# 1_AIR_TEST.net
KiCad netlist of a schematic drawn in Altium Designer
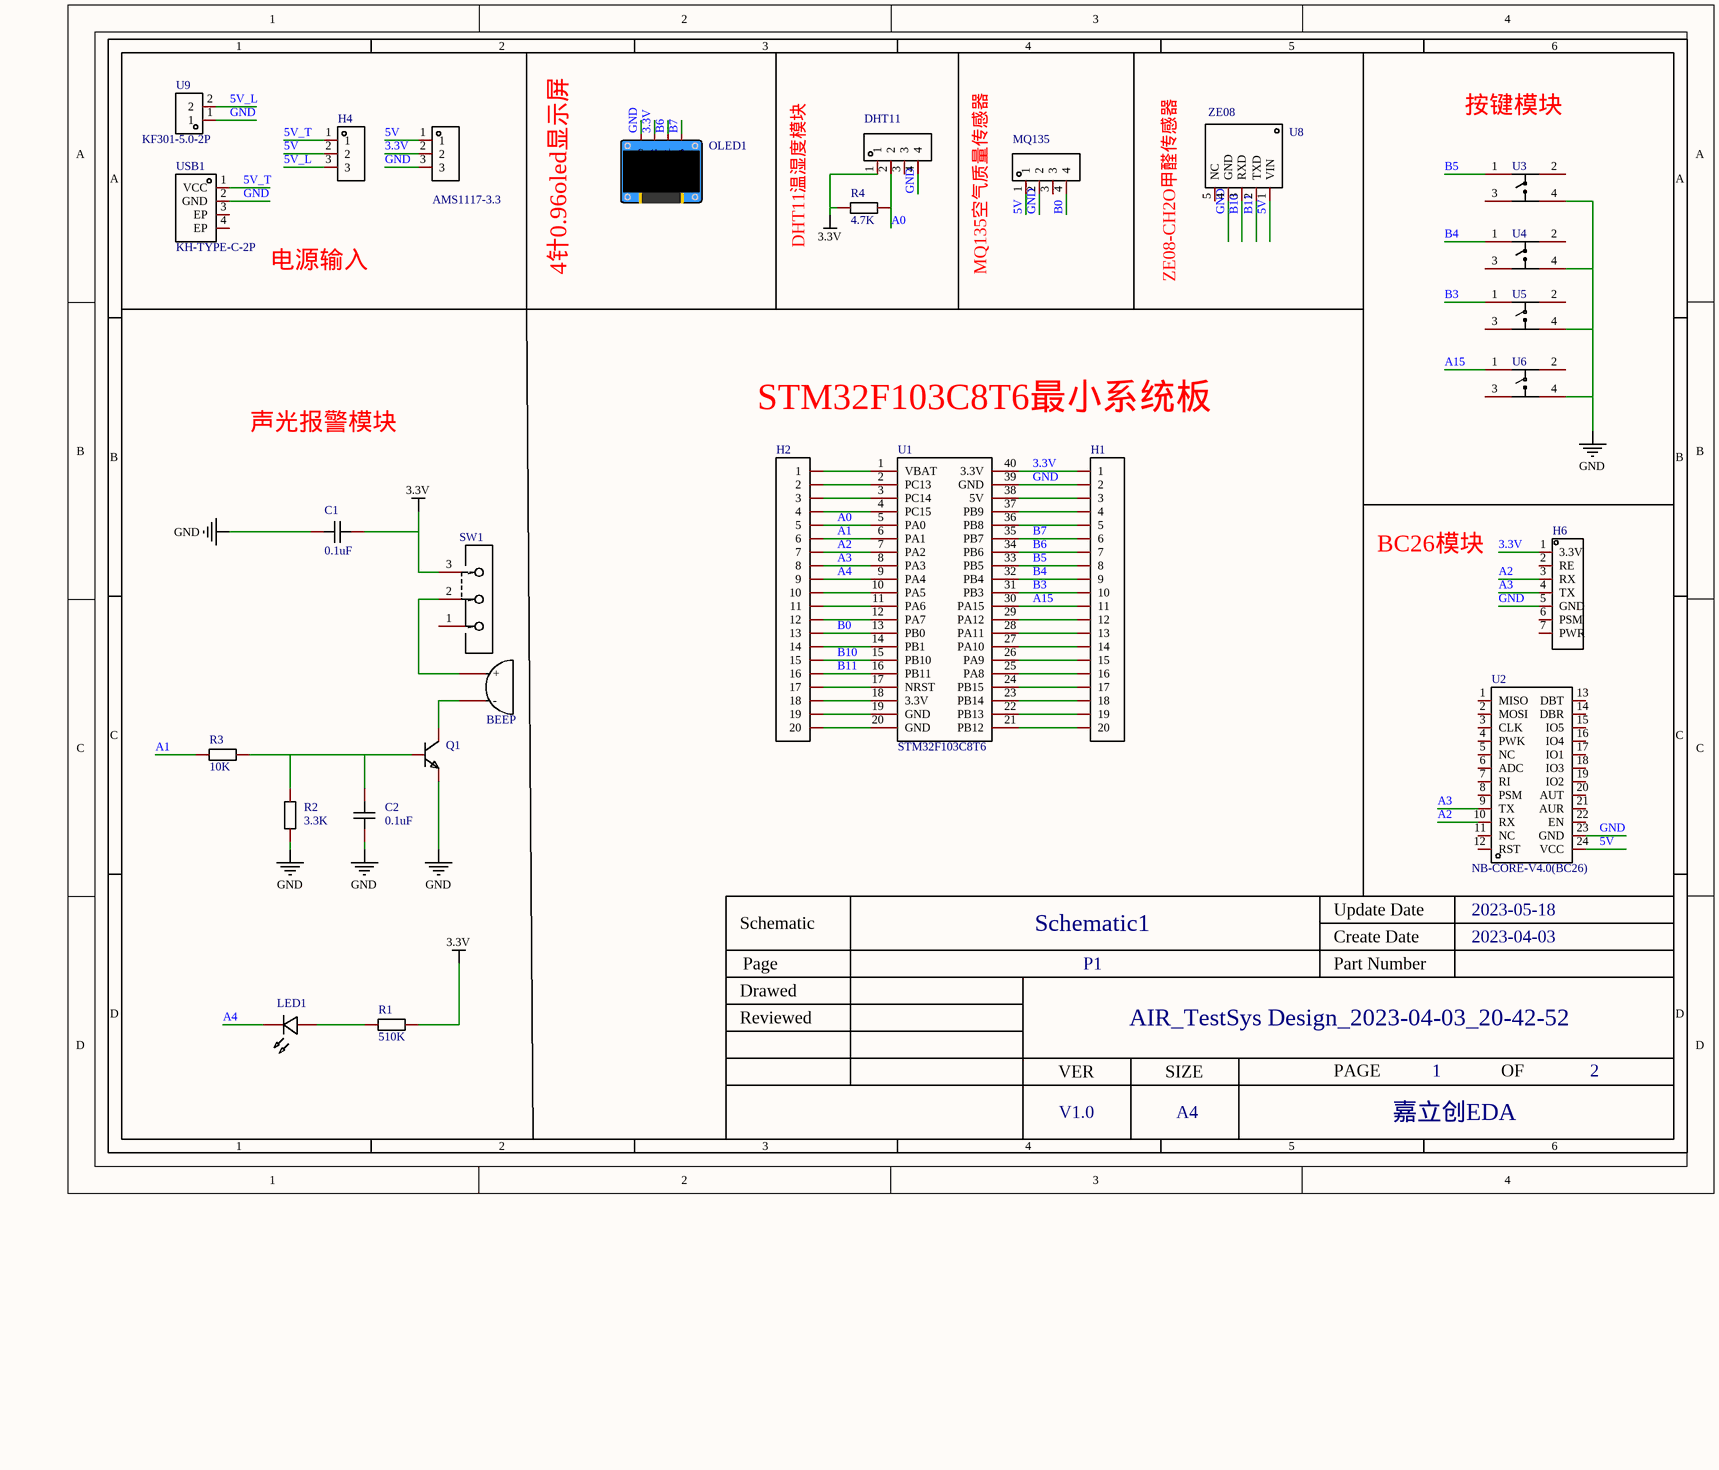
[diagram p0: 1_AIR_TEST.schdoc]

(export (version "E")
  (design (tool "Eeschema 10.0.6"))
  (components
    (comp (ref "BEEP1")
      (value "BEEP")
      (fields (field (name "NAME") "BEEP"))
      (libsource (lib "altium-import") (part "root_3_BEEP_"))
    )
    (comp (ref "C1")
      (value "0.1uF")
      (fields (field (name "NAME") "0.1uF"))
      (libsource (lib "altium-import") (part "root_0_CAP_0603_"))
    )
    (comp (ref "C2")
      (value "0.1uF")
      (fields (field (name "NAME") "0.1uF"))
      (libsource (lib "altium-import") (part "root_1_CAP_0603_"))
    )
    (comp (ref "DHT11")
      (value "HDR-F_2.54_1x4P")
      (libsource (lib "altium-import") (part "root_1_HDR-F_2.54_1x4P_"))
    )
    (comp (ref "H1")
      (value "HDR-F_2.54_1x20P")
      (libsource (lib "altium-import") (part "root_0_HDR-F_2.54_1x20P_"))
    )
    (comp (ref "H2")
      (value "HDR-F_2.54_1x20P")
      (libsource (lib "altium-import") (part "root_0_mirrored_HDR-F_2.54_1x20P_"))
    )
    (comp (ref "H4")
      (value "HDR-F_2.54_1x3P")
      (libsource (lib "altium-import") (part "root_0_HDR-F_2.54_1x3P_"))
    )
    (comp (ref "H6")
      (value "HDR-F_2.54_1x7P")
      (libsource (lib "altium-import") (part "root_0_HDR-F_2.54_1x7P_"))
    )
    (comp (ref "LED1") (value "LED_TH-R_3mm") (libsource (lib "altium-import") (part "root_2_LED_TH-R_3mm_")))
    (comp (ref "MQ135")
      (value "HDR-F_2.54_1x4P")
      (libsource (lib "altium-import") (part "root_1_HDR-F_2.54_1x4P_"))
    )
    (comp (ref "OLED1")
      (value "0.96OLED模块_4P")
      (libsource (lib "altium-import") (part "root_0_0.96OLED模块_4P_"))
    )
    (comp (ref "Q1") (value "S8050_TO_NPN") (libsource (lib "altium-import") (part "root_0_S8050_TO_NPN_")))
    (comp (ref "R1")
      (value "510K")
      (fields (field (name "NAME") "510K"))
      (libsource (lib "altium-import") (part "root_0_Res_0603_"))
    )
    (comp (ref "R2")
      (value "3.3K")
      (fields (field (name "NAME") "3.3K"))
      (libsource (lib "altium-import") (part "root_1_Res_0603_"))
    )
    (comp (ref "R3")
      (value "10K")
      (fields (field (name "NAME") "10K"))
      (libsource (lib "altium-import") (part "root_0_Res_0603_"))
    )
    (comp (ref "R4")
      (value "4.7K")
      (fields (field (name "NAME") "4.7K"))
      (libsource (lib "altium-import") (part "root_0_Res_0603_"))
    )
    (comp (ref "SW1")
      (value "ss-12d00-g4拨动开关")
      (fields (field (name "MANUFACTURER PART") "SS-12d00-G4"))
      (libsource (lib "altium-import") (part "root_1_ss-12d00-g4拨动开关_"))
    )
    (comp (ref "U1")
      (value "STM32F103C8T6")
      (fields
        (field (name "NAME") "STM32F103C8T6")
        (field (name "MANUFACTURER") "无")
        (field (name "MANUFACTURER PART") "STM32F103C8T6最小系统模块")
      )
      (libsource (lib "altium-import") (part "root_0_STM32F103C8T6_"))
    )
    (comp (ref "U2")
      (value "NB-CORE-V4.0(BC26)")
      (fields (field (name "NAME") "NB-CORE-V4.0(BC26)"))
      (libsource (lib "altium-import") (part "root_0_NB-CORE-V4.0(BC26)_"))
    )
    (comp (ref "U3") (value "四角按键") (libsource (lib "altium-import") (part "root_0_四角按键_")))
    (comp (ref "U4") (value "四角按键") (libsource (lib "altium-import") (part "root_0_四角按键_")))
    (comp (ref "U5") (value "四角按键") (libsource (lib "altium-import") (part "root_0_四角按键_")))
    (comp (ref "U6") (value "四角按键") (libsource (lib "altium-import") (part "root_0_四角按键_")))
    (comp (ref "U7")
      (value "AMS1117-3.3")
      (fields (field (name "NAME") "AMS1117-3.3"))
      (libsource (lib "altium-import") (part "root_0_HDR-F_2.54_1x3P_"))
    )
    (comp (ref "U8")
      (value "ZE08")
      (fields (field (name "NAME") "ZE08"))
      (libsource (lib "altium-import") (part "root_3_ZE08B_"))
    )
    (comp (ref "U9")
      (value "KF301-5.0-2P")
      (fields (field (name "NAME") "KF301-5.0-2P") (field (name "MANUFACTURER") "Cixi Kefa Elec"))
      (libsource (lib "altium-import") (part "root_2_KF301-5.0-2P_"))
    )
    (comp (ref "USB1")
      (value "KH-TYPE-C-2P")
      (description "连接器类型:Type-C;标准:-;公母:母座;触点数量:2;端口数量:1;安装方式:弯插;额定电流 - 电源:-;工作温度范围:-25℃~+85℃;")
      (fields (field (name "NAME") "KH-TYPE-C-2P") (field (name "MANUFACTURER") "kinghelm(金航标)"))
      (libsource (lib "altium-import") (part "root_0_mirrored_KH-TYPE-C-2P_"))
    )
  )
  (nets
    (net (code "1") (name "/5V") (class "Default")
      (node (ref "H4") (pin "2") (pinfunction "2_2") (pintype "passive"))
      (node (ref "MQ135") (pin "1") (pinfunction "1_1") (pintype "passive"))
      (node (ref "U2") (pin "24") (pinfunction "VCC_24") (pintype "passive"))
      (node (ref "U7") (pin "1") (pinfunction "1_1") (pintype "passive"))
      (node (ref "U8") (pin "1") (pinfunction "VIN_1") (pintype "passive"))
    )
    (net (code "2") (name "/5V_L") (class "Default")
      (node (ref "H4") (pin "3") (pinfunction "3_3") (pintype "passive"))
      (node (ref "U9") (pin "2") (pinfunction "2_2") (pintype "passive"))
    )
    (net (code "3") (name "/5V_T") (class "Default")
      (node (ref "H4") (pin "1") (pinfunction "1_1") (pintype "passive"))
      (node (ref "USB1") (pin "1") (pinfunction "VCC_1") (pintype "passive"))
    )
    (net (code "4") (name "/A0") (class "Default")
      (node (ref "DHT11") (pin "2") (pinfunction "2_2") (pintype "passive"))
      (node (ref "H2") (pin "5") (pinfunction "5_5") (pintype "passive"))
      (node (ref "R4") (pin "2") (pinfunction "2_2") (pintype "passive"))
      (node (ref "U1") (pin "5") (pinfunction "PA0_5") (pintype "passive"))
    )
    (net (code "5") (name "/A1") (class "Default")
      (node (ref "H2") (pin "6") (pinfunction "6_6") (pintype "passive"))
      (node (ref "R3") (pin "1") (pinfunction "1_1") (pintype "passive"))
      (node (ref "U1") (pin "6") (pinfunction "PA1_6") (pintype "passive"))
    )
    (net (code "6") (name "/A2") (class "Default")
      (node (ref "H2") (pin "7") (pinfunction "7_7") (pintype "passive"))
      (node (ref "H6") (pin "3") (pinfunction "RX_3") (pintype "passive"))
      (node (ref "U1") (pin "7") (pinfunction "PA2_7") (pintype "passive"))
      (node (ref "U2") (pin "10") (pinfunction "RX_10") (pintype "passive"))
    )
    (net (code "7") (name "/A3") (class "Default")
      (node (ref "H2") (pin "8") (pinfunction "8_8") (pintype "passive"))
      (node (ref "H6") (pin "4") (pinfunction "TX_4") (pintype "passive"))
      (node (ref "U1") (pin "8") (pinfunction "PA3_8") (pintype "passive"))
      (node (ref "U2") (pin "9") (pinfunction "TX_9") (pintype "passive"))
    )
    (net (code "8") (name "/A4") (class "Default")
      (node (ref "H2") (pin "9") (pinfunction "9_9") (pintype "passive"))
      (node (ref "LED1") (pin "2") (pinfunction "A_2") (pintype "passive"))
      (node (ref "U1") (pin "9") (pinfunction "PA4_9") (pintype "passive"))
    )
    (net (code "9") (name "/A15") (class "Default")
      (node (ref "H1") (pin "11") (pinfunction "11_11") (pintype "passive"))
      (node (ref "U1") (pin "30") (pinfunction "PA15_30") (pintype "passive"))
      (node (ref "U6") (pin "1") (pinfunction "1_1") (pintype "passive"))
    )
    (net (code "10") (name "/B0") (class "Default")
      (node (ref "H2") (pin "13") (pinfunction "13_13") (pintype "passive"))
      (node (ref "MQ135") (pin "4") (pinfunction "4_4") (pintype "passive"))
      (node (ref "U1") (pin "13") (pinfunction "PB0_13") (pintype "passive"))
    )
    (net (code "11") (name "/B3") (class "Default")
      (node (ref "H1") (pin "10") (pinfunction "10_10") (pintype "passive"))
      (node (ref "U1") (pin "31") (pinfunction "PB3_31") (pintype "passive"))
      (node (ref "U5") (pin "1") (pinfunction "1_1") (pintype "passive"))
    )
    (net (code "12") (name "/B4") (class "Default")
      (node (ref "H1") (pin "9") (pinfunction "9_9") (pintype "passive"))
      (node (ref "U1") (pin "32") (pinfunction "PB4_32") (pintype "passive"))
      (node (ref "U4") (pin "1") (pinfunction "1_1") (pintype "passive"))
    )
    (net (code "13") (name "/B5") (class "Default")
      (node (ref "H1") (pin "8") (pinfunction "8_8") (pintype "passive"))
      (node (ref "U1") (pin "33") (pinfunction "PB5_33") (pintype "passive"))
      (node (ref "U3") (pin "1") (pinfunction "1_1") (pintype "passive"))
    )
    (net (code "14") (name "/B6") (class "Default")
      (node (ref "H1") (pin "7") (pinfunction "7_7") (pintype "passive"))
      (node (ref "OLED1") (pin "3") (pinfunction "SCL_3") (pintype "passive"))
      (node (ref "U1") (pin "34") (pinfunction "PB6_34") (pintype "passive"))
    )
    (net (code "15") (name "/B7") (class "Default")
      (node (ref "H1") (pin "6") (pinfunction "6_6") (pintype "passive"))
      (node (ref "OLED1") (pin "4") (pinfunction "SDA_4") (pintype "passive"))
      (node (ref "U1") (pin "35") (pinfunction "PB7_35") (pintype "passive"))
    )
    (net (code "16") (name "/B10") (class "Default")
      (node (ref "H2") (pin "15") (pinfunction "15_15") (pintype "passive"))
      (node (ref "U1") (pin "15") (pinfunction "PB10_15") (pintype "passive"))
      (node (ref "U8") (pin "3") (pinfunction "RXD_3") (pintype "passive"))
    )
    (net (code "17") (name "/B11") (class "Default")
      (node (ref "H2") (pin "16") (pinfunction "16_16") (pintype "passive"))
      (node (ref "U1") (pin "16") (pinfunction "PB11_16") (pintype "passive"))
      (node (ref "U8") (pin "2") (pinfunction "TXD_2") (pintype "passive"))
    )
    (net (code "18") (name "3.3V") (class "Default")
      (node (ref "C1") (pin "2") (pinfunction "2_2") (pintype "passive"))
      (node (ref "DHT11") (pin "1") (pinfunction "1_1") (pintype "passive"))
      (node (ref "H1") (pin "1") (pinfunction "1_1") (pintype "passive"))
      (node (ref "H6") (pin "1") (pinfunction "3.3V_1") (pintype "passive"))
      (node (ref "OLED1") (pin "2") (pinfunction "VCC_2") (pintype "passive"))
      (node (ref "R1") (pin "2") (pinfunction "2_2") (pintype "passive"))
      (node (ref "R4") (pin "1") (pinfunction "1_1") (pintype "passive"))
      (node (ref "SW1") (pin "3") (pinfunction "3_3") (pintype "passive"))
      (node (ref "U1") (pin "40") (pinfunction "3.3V_40") (pintype "passive"))
      (node (ref "U7") (pin "2") (pinfunction "2_2") (pintype "passive"))
    )
    (net (code "19") (name "GND") (class "Default")
      (node (ref "C1") (pin "1") (pinfunction "1_1") (pintype "passive"))
      (node (ref "C2") (pin "1") (pinfunction "1_1") (pintype "passive"))
      (node (ref "DHT11") (pin "4") (pinfunction "4_4") (pintype "passive"))
      (node (ref "H1") (pin "2") (pinfunction "2_2") (pintype "passive"))
      (node (ref "H6") (pin "5") (pinfunction "GND_5") (pintype "passive"))
      (node (ref "MQ135") (pin "2") (pinfunction "2_2") (pintype "passive"))
      (node (ref "OLED1") (pin "1") (pinfunction "GND_1") (pintype "passive"))
      (node (ref "Q1") (pin "1") (pinfunction "E_1") (pintype "passive"))
      (node (ref "R2") (pin "1") (pinfunction "1_1") (pintype "passive"))
      (node (ref "U1") (pin "39") (pinfunction "GND_39") (pintype "passive"))
      (node (ref "U2") (pin "23") (pinfunction "GND_23") (pintype "passive"))
      (node (ref "U3") (pin "4") (pinfunction "4_4") (pintype "passive"))
      (node (ref "U4") (pin "4") (pinfunction "4_4") (pintype "passive"))
      (node (ref "U5") (pin "4") (pinfunction "4_4") (pintype "passive"))
      (node (ref "U6") (pin "4") (pinfunction "4_4") (pintype "passive"))
      (node (ref "U7") (pin "3") (pinfunction "3_3") (pintype "passive"))
      (node (ref "U8") (pin "4") (pinfunction "GND_4") (pintype "passive"))
      (node (ref "U9") (pin "1") (pinfunction "1_1") (pintype "passive"))
      (node (ref "USB1") (pin "2") (pinfunction "GND_2") (pintype "passive"))
    )
    (net (code "20") (name "Net-(BEEP1-+)") (class "Default")
      (node (ref "BEEP1") (pin "1") (pinfunction "+_1") (pintype "passive"))
      (node (ref "SW1") (pin "2") (pinfunction "2_2") (pintype "passive"))
    )
    (net (code "21") (name "Net-(BEEP1--)") (class "Default")
      (node (ref "BEEP1") (pin "2") (pinfunction "-_2") (pintype "passive"))
      (node (ref "Q1") (pin "3") (pinfunction "C_3") (pintype "passive"))
    )
    (net (code "22") (name "Net-(H2-Pad18)") (class "Default")
      (node (ref "H2") (pin "18") (pinfunction "18_18") (pintype "passive"))
      (node (ref "U1") (pin "18") (pinfunction "3.3V_18") (pintype "passive"))
    )
    (net (code "23") (name "Net-(H2-Pad19)") (class "Default")
      (node (ref "H2") (pin "19") (pinfunction "19_19") (pintype "passive"))
      (node (ref "U1") (pin "19") (pinfunction "GND_19") (pintype "passive"))
    )
    (net (code "24") (name "Net-(H2-Pad20)") (class "Default")
      (node (ref "H2") (pin "20") (pinfunction "20_20") (pintype "passive"))
      (node (ref "U1") (pin "20") (pinfunction "GND_20") (pintype "passive"))
    )
    (net (code "25") (name "Net-(LED1-C)") (class "Default")
      (node (ref "LED1") (pin "1") (pinfunction "C_1") (pintype "passive"))
      (node (ref "R1") (pin "1") (pinfunction "1_1") (pintype "passive"))
    )
    (net (code "26") (name "Net-(Q1-B)") (class "Default")
      (node (ref "C2") (pin "2") (pinfunction "2_2") (pintype "passive"))
      (node (ref "Q1") (pin "2") (pinfunction "B_2") (pintype "passive"))
      (node (ref "R2") (pin "2") (pinfunction "2_2") (pintype "passive"))
      (node (ref "R3") (pin "2") (pinfunction "2_2") (pintype "passive"))
    )
    (net (code "27") (name "Net-(U1-5V)") (class "Default")
      (node (ref "H1") (pin "3") (pinfunction "3_3") (pintype "passive"))
      (node (ref "U1") (pin "38") (pinfunction "5V_38") (pintype "passive"))
    )
    (net (code "28") (name "Net-(U1-NRST)") (class "Default")
      (node (ref "H2") (pin "17") (pinfunction "17_17") (pintype "passive"))
      (node (ref "U1") (pin "17") (pinfunction "NRST_17") (pintype "passive"))
    )
    (net (code "29") (name "Net-(U1-PA5)") (class "Default")
      (node (ref "H2") (pin "10") (pinfunction "10_10") (pintype "passive"))
      (node (ref "U1") (pin "10") (pinfunction "PA5_10") (pintype "passive"))
    )
    (net (code "30") (name "Net-(U1-PA6)") (class "Default")
      (node (ref "H2") (pin "11") (pinfunction "11_11") (pintype "passive"))
      (node (ref "U1") (pin "11") (pinfunction "PA6_11") (pintype "passive"))
    )
    (net (code "31") (name "Net-(U1-PA7)") (class "Default")
      (node (ref "H2") (pin "12") (pinfunction "12_12") (pintype "passive"))
      (node (ref "U1") (pin "12") (pinfunction "PA7_12") (pintype "passive"))
    )
    (net (code "32") (name "Net-(U1-PA8)") (class "Default")
      (node (ref "H1") (pin "16") (pinfunction "16_16") (pintype "passive"))
      (node (ref "U1") (pin "25") (pinfunction "PA8_25") (pintype "passive"))
    )
    (net (code "33") (name "Net-(U1-PA9)") (class "Default")
      (node (ref "H1") (pin "15") (pinfunction "15_15") (pintype "passive"))
      (node (ref "U1") (pin "26") (pinfunction "PA9_26") (pintype "passive"))
    )
    (net (code "34") (name "Net-(U1-PA10)") (class "Default")
      (node (ref "H1") (pin "14") (pinfunction "14_14") (pintype "passive"))
      (node (ref "U1") (pin "27") (pinfunction "PA10_27") (pintype "passive"))
    )
    (net (code "35") (name "Net-(U1-PA11)") (class "Default")
      (node (ref "H1") (pin "13") (pinfunction "13_13") (pintype "passive"))
      (node (ref "U1") (pin "28") (pinfunction "PA11_28") (pintype "passive"))
    )
    (net (code "36") (name "Net-(U1-PA12)") (class "Default")
      (node (ref "H1") (pin "12") (pinfunction "12_12") (pintype "passive"))
      (node (ref "U1") (pin "29") (pinfunction "PA12_29") (pintype "passive"))
    )
    (net (code "37") (name "Net-(U1-PB1)") (class "Default")
      (node (ref "H2") (pin "14") (pinfunction "14_14") (pintype "passive"))
      (node (ref "U1") (pin "14") (pinfunction "PB1_14") (pintype "passive"))
    )
    (net (code "38") (name "Net-(U1-PB8)") (class "Default")
      (node (ref "H1") (pin "5") (pinfunction "5_5") (pintype "passive"))
      (node (ref "U1") (pin "36") (pinfunction "PB8_36") (pintype "passive"))
    )
    (net (code "39") (name "Net-(U1-PB9)") (class "Default")
      (node (ref "H1") (pin "4") (pinfunction "4_4") (pintype "passive"))
      (node (ref "U1") (pin "37") (pinfunction "PB9_37") (pintype "passive"))
    )
    (net (code "40") (name "Net-(U1-PB12)") (class "Default")
      (node (ref "H1") (pin "20") (pinfunction "20_20") (pintype "passive"))
      (node (ref "U1") (pin "21") (pinfunction "PB12_21") (pintype "passive"))
    )
    (net (code "41") (name "Net-(U1-PB13)") (class "Default")
      (node (ref "H1") (pin "19") (pinfunction "19_19") (pintype "passive"))
      (node (ref "U1") (pin "22") (pinfunction "PB13_22") (pintype "passive"))
    )
    (net (code "42") (name "Net-(U1-PB14)") (class "Default")
      (node (ref "H1") (pin "18") (pinfunction "18_18") (pintype "passive"))
      (node (ref "U1") (pin "23") (pinfunction "PB14_23") (pintype "passive"))
    )
    (net (code "43") (name "Net-(U1-PB15)") (class "Default")
      (node (ref "H1") (pin "17") (pinfunction "17_17") (pintype "passive"))
      (node (ref "U1") (pin "24") (pinfunction "PB15_24") (pintype "passive"))
    )
    (net (code "44") (name "Net-(U1-PC13)") (class "Default")
      (node (ref "H2") (pin "2") (pinfunction "2_2") (pintype "passive"))
      (node (ref "U1") (pin "2") (pinfunction "PC13_2") (pintype "passive"))
    )
    (net (code "45") (name "Net-(U1-PC14)") (class "Default")
      (node (ref "H2") (pin "3") (pinfunction "3_3") (pintype "passive"))
      (node (ref "U1") (pin "3") (pinfunction "PC14_3") (pintype "passive"))
    )
    (net (code "46") (name "Net-(U1-PC15)") (class "Default")
      (node (ref "H2") (pin "4") (pinfunction "4_4") (pintype "passive"))
      (node (ref "U1") (pin "4") (pinfunction "PC15_4") (pintype "passive"))
    )
    (net (code "47") (name "Net-(U1-VBAT)") (class "Default")
      (node (ref "H2") (pin "1") (pinfunction "1_1") (pintype "passive"))
      (node (ref "U1") (pin "1") (pinfunction "VBAT_1") (pintype "passive"))
    )
    (net (code "48") (name "unconnected-(DHT11-Pad3)") (class "Default")
      (node (ref "DHT11") (pin "3") (pinfunction "3_3") (pintype "passive"))
    )
    (net (code "49") (name "unconnected-(H6-PSM-Pad6)") (class "Default")
      (node (ref "H6") (pin "6") (pinfunction "PSM_6") (pintype "passive"))
    )
    (net (code "50") (name "unconnected-(H6-PWR-Pad7)") (class "Default")
      (node (ref "H6") (pin "7") (pinfunction "PWR_7") (pintype "passive"))
    )
    (net (code "51") (name "unconnected-(H6-RE-Pad2)") (class "Default")
      (node (ref "H6") (pin "2") (pinfunction "RE_2") (pintype "passive"))
    )
    (net (code "52") (name "unconnected-(MQ135-Pad3)") (class "Default")
      (node (ref "MQ135") (pin "3") (pinfunction "3_3") (pintype "passive"))
    )
    (net (code "53") (name "unconnected-(SW1-Pad1)") (class "Default")
      (node (ref "SW1") (pin "1") (pinfunction "1_1") (pintype "passive"))
    )
    (net (code "54") (name "unconnected-(U2-ADC-Pad6)") (class "Default")
      (node (ref "U2") (pin "6") (pinfunction "ADC_6") (pintype "passive"))
    )
    (net (code "55") (name "unconnected-(U2-AUR-Pad21)") (class "Default")
      (node (ref "U2") (pin "21") (pinfunction "AUR_21") (pintype "passive"))
    )
    (net (code "56") (name "unconnected-(U2-AUT-Pad20)") (class "Default")
      (node (ref "U2") (pin "20") (pinfunction "AUT_20") (pintype "passive"))
    )
    (net (code "57") (name "unconnected-(U2-CLK-Pad3)") (class "Default")
      (node (ref "U2") (pin "3") (pinfunction "CLK_3") (pintype "passive"))
    )
    (net (code "58") (name "unconnected-(U2-DBR-Pad14)") (class "Default")
      (node (ref "U2") (pin "14") (pinfunction "DBR_14") (pintype "passive"))
    )
    (net (code "59") (name "unconnected-(U2-DBT-Pad13)") (class "Default")
      (node (ref "U2") (pin "13") (pinfunction "DBT_13") (pintype "passive"))
    )
    (net (code "60") (name "unconnected-(U2-EN-Pad22)") (class "Default")
      (node (ref "U2") (pin "22") (pinfunction "EN_22") (pintype "passive"))
    )
    (net (code "61") (name "unconnected-(U2-IO1-Pad17)") (class "Default")
      (node (ref "U2") (pin "17") (pinfunction "IO1_17") (pintype "passive"))
    )
    (net (code "62") (name "unconnected-(U2-IO2-Pad19)") (class "Default")
      (node (ref "U2") (pin "19") (pinfunction "IO2_19") (pintype "passive"))
    )
    (net (code "63") (name "unconnected-(U2-IO3-Pad18)") (class "Default")
      (node (ref "U2") (pin "18") (pinfunction "IO3_18") (pintype "passive"))
    )
    (net (code "64") (name "unconnected-(U2-IO4-Pad16)") (class "Default")
      (node (ref "U2") (pin "16") (pinfunction "IO4_16") (pintype "passive"))
    )
    (net (code "65") (name "unconnected-(U2-IO5-Pad15)") (class "Default")
      (node (ref "U2") (pin "15") (pinfunction "IO5_15") (pintype "passive"))
    )
    (net (code "66") (name "unconnected-(U2-MISO-Pad1)") (class "Default")
      (node (ref "U2") (pin "1") (pinfunction "MISO_1") (pintype "passive"))
    )
    (net (code "67") (name "unconnected-(U2-MOSI-Pad2)") (class "Default")
      (node (ref "U2") (pin "2") (pinfunction "MOSI_2") (pintype "passive"))
    )
    (net (code "68") (name "unconnected-(U2-NC-Pad5)") (class "Default")
      (node (ref "U2") (pin "5") (pinfunction "NC_5") (pintype "passive"))
    )
    (net (code "69") (name "unconnected-(U2-NC-Pad11)") (class "Default")
      (node (ref "U2") (pin "11") (pinfunction "NC_11") (pintype "passive"))
    )
    (net (code "70") (name "unconnected-(U2-PSM-Pad8)") (class "Default")
      (node (ref "U2") (pin "8") (pinfunction "PSM_8") (pintype "passive"))
    )
    (net (code "71") (name "unconnected-(U2-PWK-Pad4)") (class "Default")
      (node (ref "U2") (pin "4") (pinfunction "PWK_4") (pintype "passive"))
    )
    (net (code "72") (name "unconnected-(U2-RI-Pad7)") (class "Default")
      (node (ref "U2") (pin "7") (pinfunction "RI_7") (pintype "passive"))
    )
    (net (code "73") (name "unconnected-(U2-RST-Pad12)") (class "Default")
      (node (ref "U2") (pin "12") (pinfunction "RST_12") (pintype "passive"))
    )
    (net (code "74") (name "unconnected-(U3-Pad2)") (class "Default")
      (node (ref "U3") (pin "2") (pinfunction "2_2") (pintype "passive"))
    )
    (net (code "75") (name "unconnected-(U3-Pad3)") (class "Default")
      (node (ref "U3") (pin "3") (pinfunction "3_3") (pintype "passive"))
    )
    (net (code "76") (name "unconnected-(U4-Pad2)") (class "Default")
      (node (ref "U4") (pin "2") (pinfunction "2_2") (pintype "passive"))
    )
    (net (code "77") (name "unconnected-(U4-Pad3)") (class "Default")
      (node (ref "U4") (pin "3") (pinfunction "3_3") (pintype "passive"))
    )
    (net (code "78") (name "unconnected-(U5-Pad2)") (class "Default")
      (node (ref "U5") (pin "2") (pinfunction "2_2") (pintype "passive"))
    )
    (net (code "79") (name "unconnected-(U5-Pad3)") (class "Default")
      (node (ref "U5") (pin "3") (pinfunction "3_3") (pintype "passive"))
    )
    (net (code "80") (name "unconnected-(U6-Pad2)") (class "Default")
      (node (ref "U6") (pin "2") (pinfunction "2_2") (pintype "passive"))
    )
    (net (code "81") (name "unconnected-(U6-Pad3)") (class "Default")
      (node (ref "U6") (pin "3") (pinfunction "3_3") (pintype "passive"))
    )
    (net (code "82") (name "unconnected-(U8-NC-Pad5)") (class "Default")
      (node (ref "U8") (pin "5") (pinfunction "NC_5") (pintype "passive"))
    )
    (net (code "83") (name "unconnected-(USB1-EP-Pad3)") (class "Default")
      (node (ref "USB1") (pin "3") (pinfunction "EP_3") (pintype "passive"))
    )
    (net (code "84") (name "unconnected-(USB1-EP-Pad4)") (class "Default")
      (node (ref "USB1") (pin "4") (pinfunction "EP_4") (pintype "passive"))
    )
  )
)
